# EXP03_2307_20232241110.net
KiCad netlist of a schematic drawn in Altium Designer
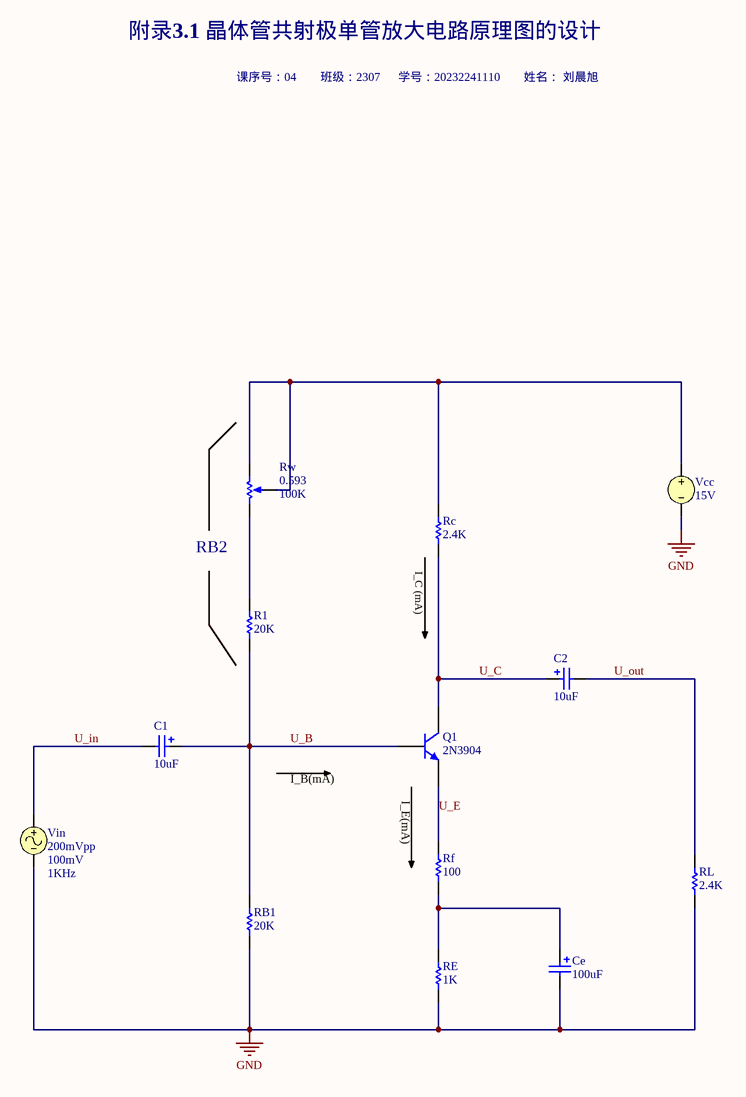
[diagram p0: EXP03_2307_20232241110.SchDoc]

(export (version "E")
  (design (tool "Eeschema 10.0.6"))
  (components
    (comp (ref "C1")
      (value "10uF")
      (footprint "POLAR0.8")
      (description "Polarized Capacitor (Axial)")
      (fields (field (name "Comment") "Cap Pol2") (field (name "PUBLISHER") "Altium Limited"))
      (libsource (lib "") (part "Cap Pol2_1"))
    )
    (comp (ref "C2")
      (value "10uF")
      (footprint "POLAR0.8")
      (description "Polarized Capacitor (Axial)")
      (fields (field (name "Comment") "Cap Pol2") (field (name "PUBLISHER") "Altium Limited"))
      (libsource (lib "") (part "Cap Pol2_1"))
    )
    (comp (ref "Ce")
      (value "100uF")
      (footprint "POLAR0.8")
      (description "Polarized Capacitor (Axial)")
      (fields (field (name "Comment") "Cap Pol2") (field (name "PUBLISHER") "Altium Limited"))
      (libsource (lib "Miscellaneous Devices") (part "Cap Pol2"))
    )
    (comp (ref "Q1")
      (value "2N3904")
      (footprint "TO-92A")
      (description "NPN General Purpose Amplifier")
      (fields (field (name "PUBLISHER") "Altium Limited"))
      (libsource (lib "Miscellaneous Devices") (part "2N3904"))
    )
    (comp (ref "R1")
      (value "20K")
      (footprint "AXIAL-0.3")
      (description "Resistor")
      (fields (field (name "Comment") "Res1") (field (name "PUBLISHER") "Altium Limited"))
      (libsource (lib "Miscellaneous Devices") (part "Res1"))
    )
    (comp (ref "RB1")
      (value "20K")
      (footprint "AXIAL-0.3")
      (description "Resistor")
      (fields (field (name "Comment") "Res1") (field (name "PUBLISHER") "Altium Limited"))
      (libsource (lib "Miscellaneous Devices") (part "Res1"))
    )
    (comp (ref "Rc")
      (value "2.4K")
      (footprint "AXIAL-0.3")
      (description "Resistor")
      (fields (field (name "Comment") "Res1") (field (name "PUBLISHER") "Altium Limited"))
      (libsource (lib "Miscellaneous Devices") (part "Res1"))
    )
    (comp (ref "RE")
      (value "1K")
      (footprint "AXIAL-0.3")
      (description "Resistor")
      (fields (field (name "Comment") "Res1") (field (name "PUBLISHER") "Altium Limited"))
      (libsource (lib "Miscellaneous Devices") (part "Res1"))
    )
    (comp (ref "Rf")
      (value "100")
      (footprint "AXIAL-0.3")
      (description "Resistor")
      (fields (field (name "Comment") "Res1") (field (name "PUBLISHER") "Altium Limited"))
      (libsource (lib "Miscellaneous Devices") (part "Res1"))
    )
    (comp (ref "RL")
      (value "2.4K")
      (footprint "AXIAL-0.3")
      (description "Resistor")
      (fields (field (name "Comment") "Res1") (field (name "PUBLISHER") "Altium Limited"))
      (libsource (lib "Miscellaneous Devices") (part "Res1"))
    )
    (comp (ref "Rw")
      (value "100K")
      (footprint "VR5")
      (description "Potentiometer")
      (fields
        (field (name "SET POSITION") "0.593")
        (field (name "Comment") "RPot")
        (field (name "PUBLISHER") "Altium Limited")
      )
      (libsource (lib "Miscellaneous Devices") (part "RPot"))
    )
    (comp (ref "Vcc")
      (value "15V")
      (description "Voltage Source")
      (fields (field (name "Comment") "VSRC") (field (name "PUBLISHER") "Altium Limited"))
      (libsource (lib "Simulation Sources") (part "VSRC"))
    )
    (comp (ref "Vin")
      (value "200mVpp")
      (description "Sinusoidal Voltage Source")
      (fields
        (field (name "AMPLITUDE") "100mV")
        (field (name "FREQUENCY") "1KHz")
        (field (name "PUBLISHER") "Altium Limited")
      )
      (libsource (lib "Simulation Sources") (part "VSIN"))
    )
  )
  (nets
    (net (code "1") (name "/U_B") (class "Default")
      (node (ref "C1") (pin "1") (pinfunction "1_1") (pintype "passive"))
      (node (ref "Q1") (pin "2") (pinfunction "B_2") (pintype "passive"))
      (node (ref "R1") (pin "1") (pinfunction "1_1") (pintype "passive"))
      (node (ref "RB1") (pin "2") (pinfunction "2_2") (pintype "passive"))
    )
    (net (code "2") (name "/U_C") (class "Default")
      (node (ref "C2") (pin "1") (pinfunction "1_1") (pintype "passive"))
      (node (ref "Q1") (pin "3") (pinfunction "C_3") (pintype "passive"))
      (node (ref "Rc") (pin "1") (pinfunction "1_1") (pintype "passive"))
    )
    (net (code "3") (name "/U_E") (class "Default")
      (node (ref "Q1") (pin "1") (pinfunction "E_1") (pintype "passive"))
      (node (ref "Rf") (pin "2") (pinfunction "2_2") (pintype "passive"))
    )
    (net (code "4") (name "/U_in") (class "Default")
      (node (ref "C1") (pin "2") (pinfunction "2_2") (pintype "passive"))
      (node (ref "Vin") (pin "1") (pinfunction "1_1") (pintype "passive"))
    )
    (net (code "5") (name "/U_out") (class "Default")
      (node (ref "C2") (pin "2") (pinfunction "2_2") (pintype "passive"))
      (node (ref "RL") (pin "2") (pinfunction "2_2") (pintype "passive"))
    )
    (net (code "6") (name "GND") (class "Default")
      (node (ref "Ce") (pin "2") (pinfunction "2_2") (pintype "passive"))
      (node (ref "RB1") (pin "1") (pinfunction "1_1") (pintype "passive"))
      (node (ref "RE") (pin "1") (pinfunction "1_1") (pintype "passive"))
      (node (ref "RL") (pin "1") (pinfunction "1_1") (pintype "passive"))
      (node (ref "Vcc") (pin "2") (pinfunction "2_2") (pintype "passive"))
      (node (ref "Vin") (pin "2") (pinfunction "2_2") (pintype "passive"))
    )
    (net (code "7") (name "Net-(Ce-Pad1)") (class "Default")
      (node (ref "Ce") (pin "1") (pinfunction "1_1") (pintype "passive"))
      (node (ref "RE") (pin "2") (pinfunction "2_2") (pintype "passive"))
      (node (ref "Rf") (pin "1") (pinfunction "1_1") (pintype "passive"))
    )
    (net (code "8") (name "Net-(Rw-BOT)") (class "Default")
      (node (ref "R1") (pin "2") (pinfunction "2_2") (pintype "passive"))
      (node (ref "Rw") (pin "2") (pinfunction "BOT_2") (pintype "passive"))
    )
    (net (code "9") (name "Net-(Rw-TAP)") (class "Default")
      (node (ref "Rc") (pin "2") (pinfunction "2_2") (pintype "passive"))
      (node (ref "Rw") (pin "1") (pinfunction "TOP_1") (pintype "passive"))
      (node (ref "Rw") (pin "3") (pinfunction "TAP_3") (pintype "passive"))
      (node (ref "Vcc") (pin "1") (pinfunction "1_1") (pintype "passive"))
    )
  )
)
